# o2_sensor_interface.net
KiCad netlist of a schematic drawn in EAGLE
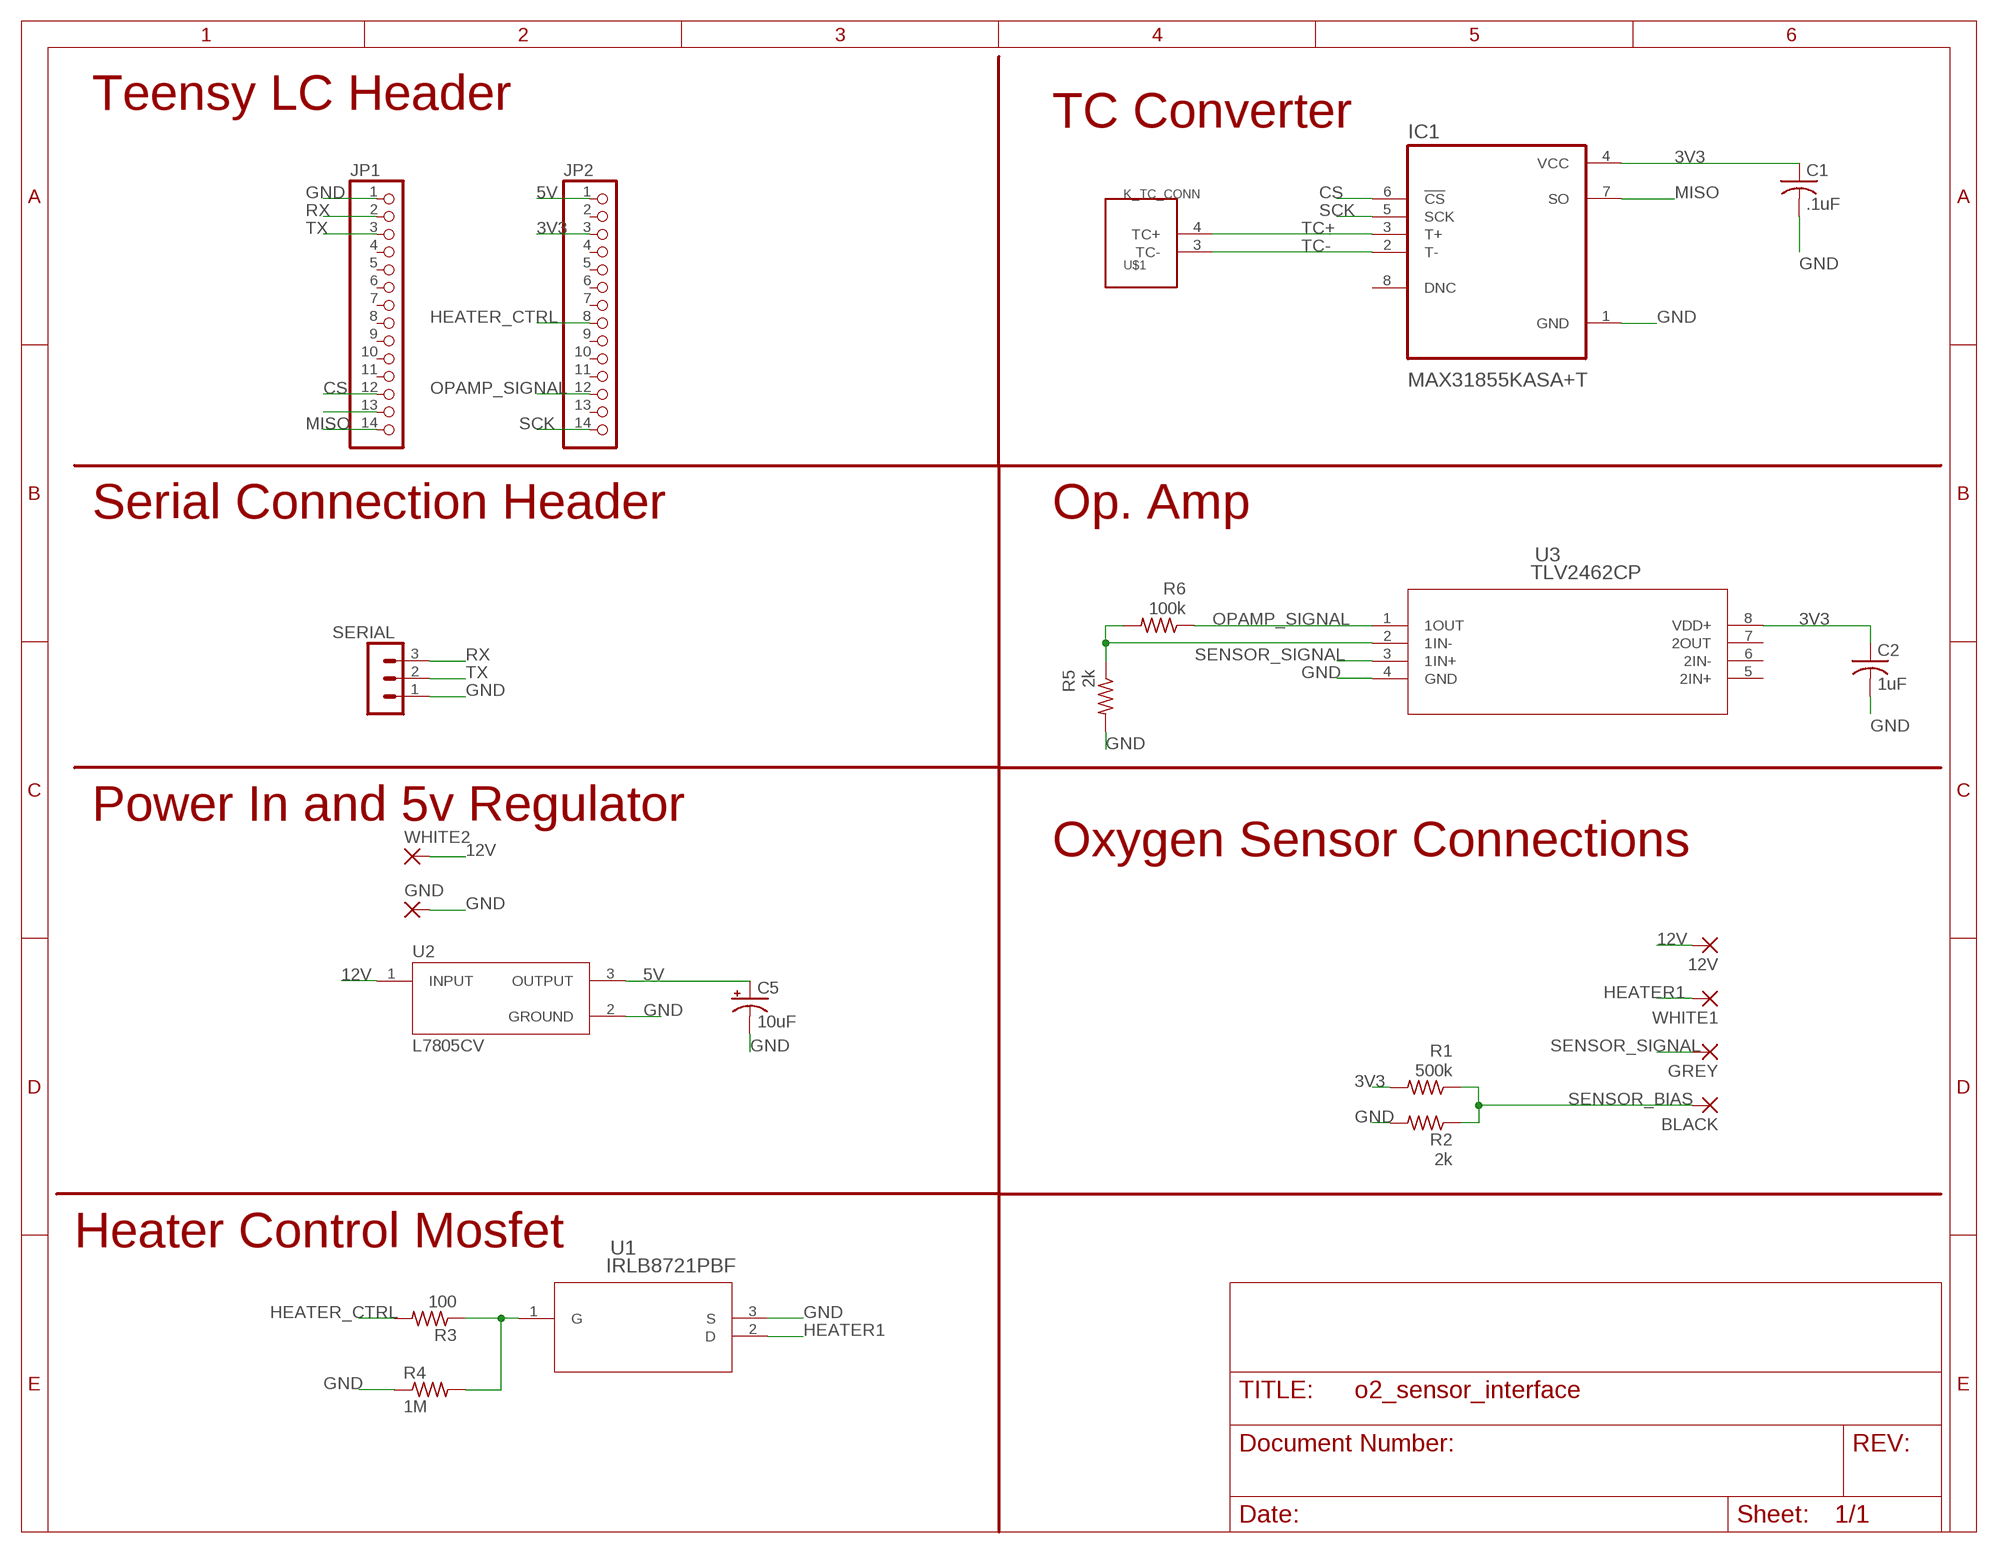
[diagram p0: schematic, sheet 1]

(export (version "E")
  (design (tool "Eeschema 10.0.6"))
  (components
    (comp (ref "12V")
      (value "3,17/1,3")
      (footprint "eagle-import:3,17_1,3")
      (libsource (lib "eagle-import") (part "3,17/1,3"))
    )
    (comp (ref "BLACK")
      (value "3,17/1,3")
      (footprint "eagle-import:3,17_1,3")
      (libsource (lib "eagle-import") (part "3,17/1,3"))
    )
    (comp (ref "C1")
      (value ".1uF")
      (footprint "eagle-import:C025-030X050")
      (libsource (lib "eagle-import") (part "C-US025-030X050"))
    )
    (comp (ref "C2")
      (value "1uF")
      (footprint "eagle-import:C025-030X050")
      (libsource (lib "eagle-import") (part "C-US025-030X050"))
    )
    (comp (ref "C5")
      (value "10uF")
      (footprint "eagle-import:E2-4")
      (libsource (lib "eagle-import") (part "CPOL-USE2-4"))
    )
    (comp (ref "GND")
      (value "3,17/1,3")
      (footprint "eagle-import:3,17_1,3")
      (libsource (lib "eagle-import") (part "3,17/1,3"))
    )
    (comp (ref "GREY")
      (value "3,17/1,3")
      (footprint "eagle-import:3,17_1,3")
      (libsource (lib "eagle-import") (part "3,17/1,3"))
    )
    (comp (ref "IC1")
      (value "MAX31855KASA+T")
      (footprint "eagle-import:SOIC127P600X175-8N")
      (fields
        (field (name "DIGI-KEY_PART_NUMBER") "MAX31855KASA+TCT-ND")
        (field (name "MF") "Maxim Integrated")
      )
      (libsource (lib "eagle-import") (part "MAX31855KASA+T"))
    )
    (comp (ref "JP1")
      (value "PINHD-1X14")
      (footprint "eagle-import:1X14")
      (libsource (lib "eagle-import") (part "PINHD-1X14"))
    )
    (comp (ref "JP2")
      (value "PINHD-1X14")
      (footprint "eagle-import:1X14")
      (libsource (lib "eagle-import") (part "PINHD-1X14"))
    )
    (comp (ref "R1")
      (value "500k")
      (footprint "eagle-import:0207_9")
      (libsource (lib "eagle-import") (part "R-US_0207/9"))
    )
    (comp (ref "R2")
      (value "2k")
      (footprint "eagle-import:0207_9")
      (libsource (lib "eagle-import") (part "R-US_0207/9"))
    )
    (comp (ref "R3")
      (value "100")
      (footprint "eagle-import:0207_9")
      (libsource (lib "eagle-import") (part "R-US_0207/9"))
    )
    (comp (ref "R4")
      (value "1M")
      (footprint "eagle-import:0207_9")
      (libsource (lib "eagle-import") (part "R-US_0207/9"))
    )
    (comp (ref "R5")
      (value "2k")
      (footprint "eagle-import:0207_9")
      (libsource (lib "eagle-import") (part "R-US_0207/9"))
    )
    (comp (ref "R6")
      (value "100k")
      (footprint "eagle-import:0207_9")
      (libsource (lib "eagle-import") (part "R-US_0207/9"))
    )
    (comp (ref "SERIAL")
      (value "MA03-1")
      (footprint "eagle-import:MA03-1")
      (libsource (lib "eagle-import") (part "MA03-1"))
    )
    (comp (ref "U$1")
      (value "K_TC_CONN")
      (footprint "eagle-import:TC_KTYPE")
      (libsource (lib "eagle-import") (part "K_TC_CONN"))
    )
    (comp (ref "U1")
      (value "IRLB8721PBF")
      (footprint "eagle-import:PG-TO220-3")
      (fields (field (name "COPYRIGHT") "Copyright (C) 2018 Accelerated Designs. All rights reserved"))
      (libsource (lib "eagle-import") (part "IRLB8721PBF"))
    )
    (comp (ref "U2")
      (value "L7805CV")
      (footprint "eagle-import:TO255P1040X460X1968-3")
      (fields (field (name "DIGI-KEY_PART_NUMBER") "497-12404-ND") (field (name "MF") "STMicroelectronics"))
      (libsource (lib "eagle-import") (part "L7805CV"))
    )
    (comp (ref "U3")
      (value "TLV2462CP")
      (footprint "eagle-import:P8")
      (fields
        (field (name "GENERIC_PART_NUMBER") "TLV2462")
        (field (name "MANUFACTURER") "Texas Instruments")
      )
      (libsource (lib "eagle-import") (part "TLV2462CP"))
    )
    (comp (ref "WHITE1")
      (value "3,17/1,3")
      (footprint "eagle-import:3,17_1,3")
      (libsource (lib "eagle-import") (part "3,17/1,3"))
    )
    (comp (ref "WHITE2")
      (value "3,17/1,3")
      (footprint "eagle-import:3,17_1,3")
      (libsource (lib "eagle-import") (part "3,17/1,3"))
    )
  )
  (nets
    (net (code "1") (name "/3V3") (class "Default")
      (node (ref "C1") (pin "1") (pinfunction "1_1") (pintype "passive"))
      (node (ref "C2") (pin "1") (pinfunction "1_1") (pintype "passive"))
      (node (ref "IC1") (pin "4") (pinfunction "VCC_4") (pintype "power_in"))
      (node (ref "JP2") (pin "3") (pinfunction "3_3") (pintype "passive"))
      (node (ref "R1") (pin "2") (pinfunction "2_2") (pintype "passive"))
      (node (ref "U3") (pin "8") (pinfunction "VDD+_8") (pintype "power_in"))
    )
    (net (code "2") (name "/5V") (class "Default")
      (node (ref "C5") (pin "+") (pinfunction "+_+") (pintype "passive"))
      (node (ref "JP2") (pin "1") (pinfunction "1_1") (pintype "passive"))
      (node (ref "U2") (pin "3") (pinfunction "OUTPUT_3") (pintype "output"))
    )
    (net (code "3") (name "/12V") (class "Default")
      (node (ref "12V") (pin "1") (pinfunction "P_1") (pintype "passive"))
      (node (ref "U2") (pin "1") (pinfunction "INPUT_1") (pintype "input"))
      (node (ref "WHITE2") (pin "1") (pinfunction "P_1") (pintype "passive"))
    )
    (net (code "4") (name "/CS") (class "Default")
      (node (ref "IC1") (pin "6") (pinfunction "~{CS}_6") (pintype "input"))
      (node (ref "JP1") (pin "12") (pinfunction "12_12") (pintype "passive"))
    )
    (net (code "5") (name "/GND") (class "Default")
      (node (ref "C1") (pin "2") (pinfunction "2_2") (pintype "passive"))
      (node (ref "C2") (pin "2") (pinfunction "2_2") (pintype "passive"))
      (node (ref "C5") (pin "-") (pinfunction "-_-") (pintype "passive"))
      (node (ref "GND") (pin "1") (pinfunction "P_1") (pintype "passive"))
      (node (ref "IC1") (pin "1") (pinfunction "GND_1") (pintype "power_in"))
      (node (ref "JP1") (pin "1") (pinfunction "1_1") (pintype "passive"))
      (node (ref "R2") (pin "2") (pinfunction "2_2") (pintype "passive"))
      (node (ref "R4") (pin "1") (pinfunction "1_1") (pintype "passive"))
      (node (ref "R5") (pin "2") (pinfunction "2_2") (pintype "passive"))
      (node (ref "SERIAL") (pin "1") (pinfunction "1_1") (pintype "passive"))
      (node (ref "U1") (pin "3") (pinfunction "S_3") (pintype "passive"))
      (node (ref "U2") (pin "2") (pinfunction "GROUND_2") (pintype "power_in"))
      (node (ref "U3") (pin "4") (pinfunction "GND_4") (pintype "power_in"))
    )
    (net (code "6") (name "/HEATER1") (class "Default")
      (node (ref "U1") (pin "2") (pinfunction "D_2") (pintype "passive"))
      (node (ref "WHITE1") (pin "1") (pinfunction "P_1") (pintype "passive"))
    )
    (net (code "7") (name "/HEATER_CTRL") (class "Default")
      (node (ref "JP2") (pin "8") (pinfunction "8_8") (pintype "passive"))
      (node (ref "R3") (pin "2") (pinfunction "2_2") (pintype "passive"))
    )
    (net (code "8") (name "/MISO") (class "Default")
      (node (ref "IC1") (pin "7") (pinfunction "SO_7") (pintype "output"))
      (node (ref "JP1") (pin "14") (pinfunction "14_14") (pintype "passive"))
    )
    (net (code "9") (name "/OPAMP_SIGNAL") (class "Default")
      (node (ref "JP2") (pin "12") (pinfunction "12_12") (pintype "passive"))
      (node (ref "R6") (pin "1") (pinfunction "1_1") (pintype "passive"))
      (node (ref "U3") (pin "1") (pinfunction "1OUT_1") (pintype "output"))
    )
    (net (code "10") (name "/RX") (class "Default")
      (node (ref "JP1") (pin "2") (pinfunction "2_2") (pintype "passive"))
      (node (ref "SERIAL") (pin "3") (pinfunction "3_3") (pintype "passive"))
    )
    (net (code "11") (name "/SCK") (class "Default")
      (node (ref "IC1") (pin "5") (pinfunction "SCK_5") (pintype "input"))
      (node (ref "JP2") (pin "14") (pinfunction "14_14") (pintype "passive"))
    )
    (net (code "12") (name "/SENSOR_BIAS") (class "Default")
      (node (ref "BLACK") (pin "1") (pinfunction "P_1") (pintype "passive"))
      (node (ref "R1") (pin "1") (pinfunction "1_1") (pintype "passive"))
      (node (ref "R2") (pin "1") (pinfunction "1_1") (pintype "passive"))
    )
    (net (code "13") (name "/SENSOR_SIGNAL") (class "Default")
      (node (ref "GREY") (pin "1") (pinfunction "P_1") (pintype "passive"))
      (node (ref "U3") (pin "3") (pinfunction "1IN+_3") (pintype "input"))
    )
    (net (code "14") (name "/TC+") (class "Default")
      (node (ref "IC1") (pin "3") (pinfunction "T+_3") (pintype "input"))
      (node (ref "U$1") (pin "4") (pinfunction "TC+_4") (pintype "bidirectional"))
    )
    (net (code "15") (name "/TC-") (class "Default")
      (node (ref "IC1") (pin "2") (pinfunction "T-_2") (pintype "input"))
      (node (ref "U$1") (pin "3") (pinfunction "TC-_3") (pintype "bidirectional"))
    )
    (net (code "16") (name "/TX") (class "Default")
      (node (ref "JP1") (pin "3") (pinfunction "3_3") (pintype "passive"))
      (node (ref "SERIAL") (pin "2") (pinfunction "2_2") (pintype "passive"))
    )
    (net (code "17") (name "Net-(U1-G)") (class "Default")
      (node (ref "R3") (pin "1") (pinfunction "1_1") (pintype "passive"))
      (node (ref "R4") (pin "2") (pinfunction "2_2") (pintype "passive"))
      (node (ref "U1") (pin "1") (pinfunction "G_1") (pintype "passive"))
    )
    (net (code "18") (name "Net-(U3-1IN-)") (class "Default")
      (node (ref "R5") (pin "1") (pinfunction "1_1") (pintype "passive"))
      (node (ref "R6") (pin "2") (pinfunction "2_2") (pintype "passive"))
      (node (ref "U3") (pin "2") (pinfunction "1IN-_2") (pintype "input"))
    )
    (net (code "19") (name "unconnected-(IC1-DNC-Pad8)") (class "Default")
      (node (ref "IC1") (pin "8") (pinfunction "DNC_8") (pintype "bidirectional"))
    )
    (net (code "20") (name "unconnected-(JP1-Pad4)") (class "Default")
      (node (ref "JP1") (pin "4") (pinfunction "4_4") (pintype "passive"))
    )
    (net (code "21") (name "unconnected-(JP1-Pad5)") (class "Default")
      (node (ref "JP1") (pin "5") (pinfunction "5_5") (pintype "passive"))
    )
    (net (code "22") (name "unconnected-(JP1-Pad6)") (class "Default")
      (node (ref "JP1") (pin "6") (pinfunction "6_6") (pintype "passive"))
    )
    (net (code "23") (name "unconnected-(JP1-Pad7)") (class "Default")
      (node (ref "JP1") (pin "7") (pinfunction "7_7") (pintype "passive"))
    )
    (net (code "24") (name "unconnected-(JP1-Pad8)") (class "Default")
      (node (ref "JP1") (pin "8") (pinfunction "8_8") (pintype "passive"))
    )
    (net (code "25") (name "unconnected-(JP1-Pad9)") (class "Default")
      (node (ref "JP1") (pin "9") (pinfunction "9_9") (pintype "passive"))
    )
    (net (code "26") (name "unconnected-(JP1-Pad10)") (class "Default")
      (node (ref "JP1") (pin "10") (pinfunction "10_10") (pintype "passive"))
    )
    (net (code "27") (name "unconnected-(JP1-Pad11)") (class "Default")
      (node (ref "JP1") (pin "11") (pinfunction "11_11") (pintype "passive"))
    )
    (net (code "28") (name "unconnected-(JP1-Pad13)") (class "Default")
      (node (ref "JP1") (pin "13") (pinfunction "13_13") (pintype "passive"))
    )
    (net (code "29") (name "unconnected-(JP2-Pad2)") (class "Default")
      (node (ref "JP2") (pin "2") (pinfunction "2_2") (pintype "passive"))
    )
    (net (code "30") (name "unconnected-(JP2-Pad4)") (class "Default")
      (node (ref "JP2") (pin "4") (pinfunction "4_4") (pintype "passive"))
    )
    (net (code "31") (name "unconnected-(JP2-Pad5)") (class "Default")
      (node (ref "JP2") (pin "5") (pinfunction "5_5") (pintype "passive"))
    )
    (net (code "32") (name "unconnected-(JP2-Pad6)") (class "Default")
      (node (ref "JP2") (pin "6") (pinfunction "6_6") (pintype "passive"))
    )
    (net (code "33") (name "unconnected-(JP2-Pad7)") (class "Default")
      (node (ref "JP2") (pin "7") (pinfunction "7_7") (pintype "passive"))
    )
    (net (code "34") (name "unconnected-(JP2-Pad9)") (class "Default")
      (node (ref "JP2") (pin "9") (pinfunction "9_9") (pintype "passive"))
    )
    (net (code "35") (name "unconnected-(JP2-Pad10)") (class "Default")
      (node (ref "JP2") (pin "10") (pinfunction "10_10") (pintype "passive"))
    )
    (net (code "36") (name "unconnected-(JP2-Pad11)") (class "Default")
      (node (ref "JP2") (pin "11") (pinfunction "11_11") (pintype "passive"))
    )
    (net (code "37") (name "unconnected-(JP2-Pad13)") (class "Default")
      (node (ref "JP2") (pin "13") (pinfunction "13_13") (pintype "passive"))
    )
    (net (code "38") (name "unconnected-(U3-2IN+-Pad5)") (class "Default")
      (node (ref "U3") (pin "5") (pinfunction "2IN+_5") (pintype "input"))
    )
    (net (code "39") (name "unconnected-(U3-2IN--Pad6)") (class "Default")
      (node (ref "U3") (pin "6") (pinfunction "2IN-_6") (pintype "input"))
    )
    (net (code "40") (name "unconnected-(U3-2OUT-Pad7)") (class "Default")
      (node (ref "U3") (pin "7") (pinfunction "2OUT_7") (pintype "output"))
    )
  )
)
